# BME280-Breakout_v12.net
KiCad netlist of a schematic drawn in EAGLE
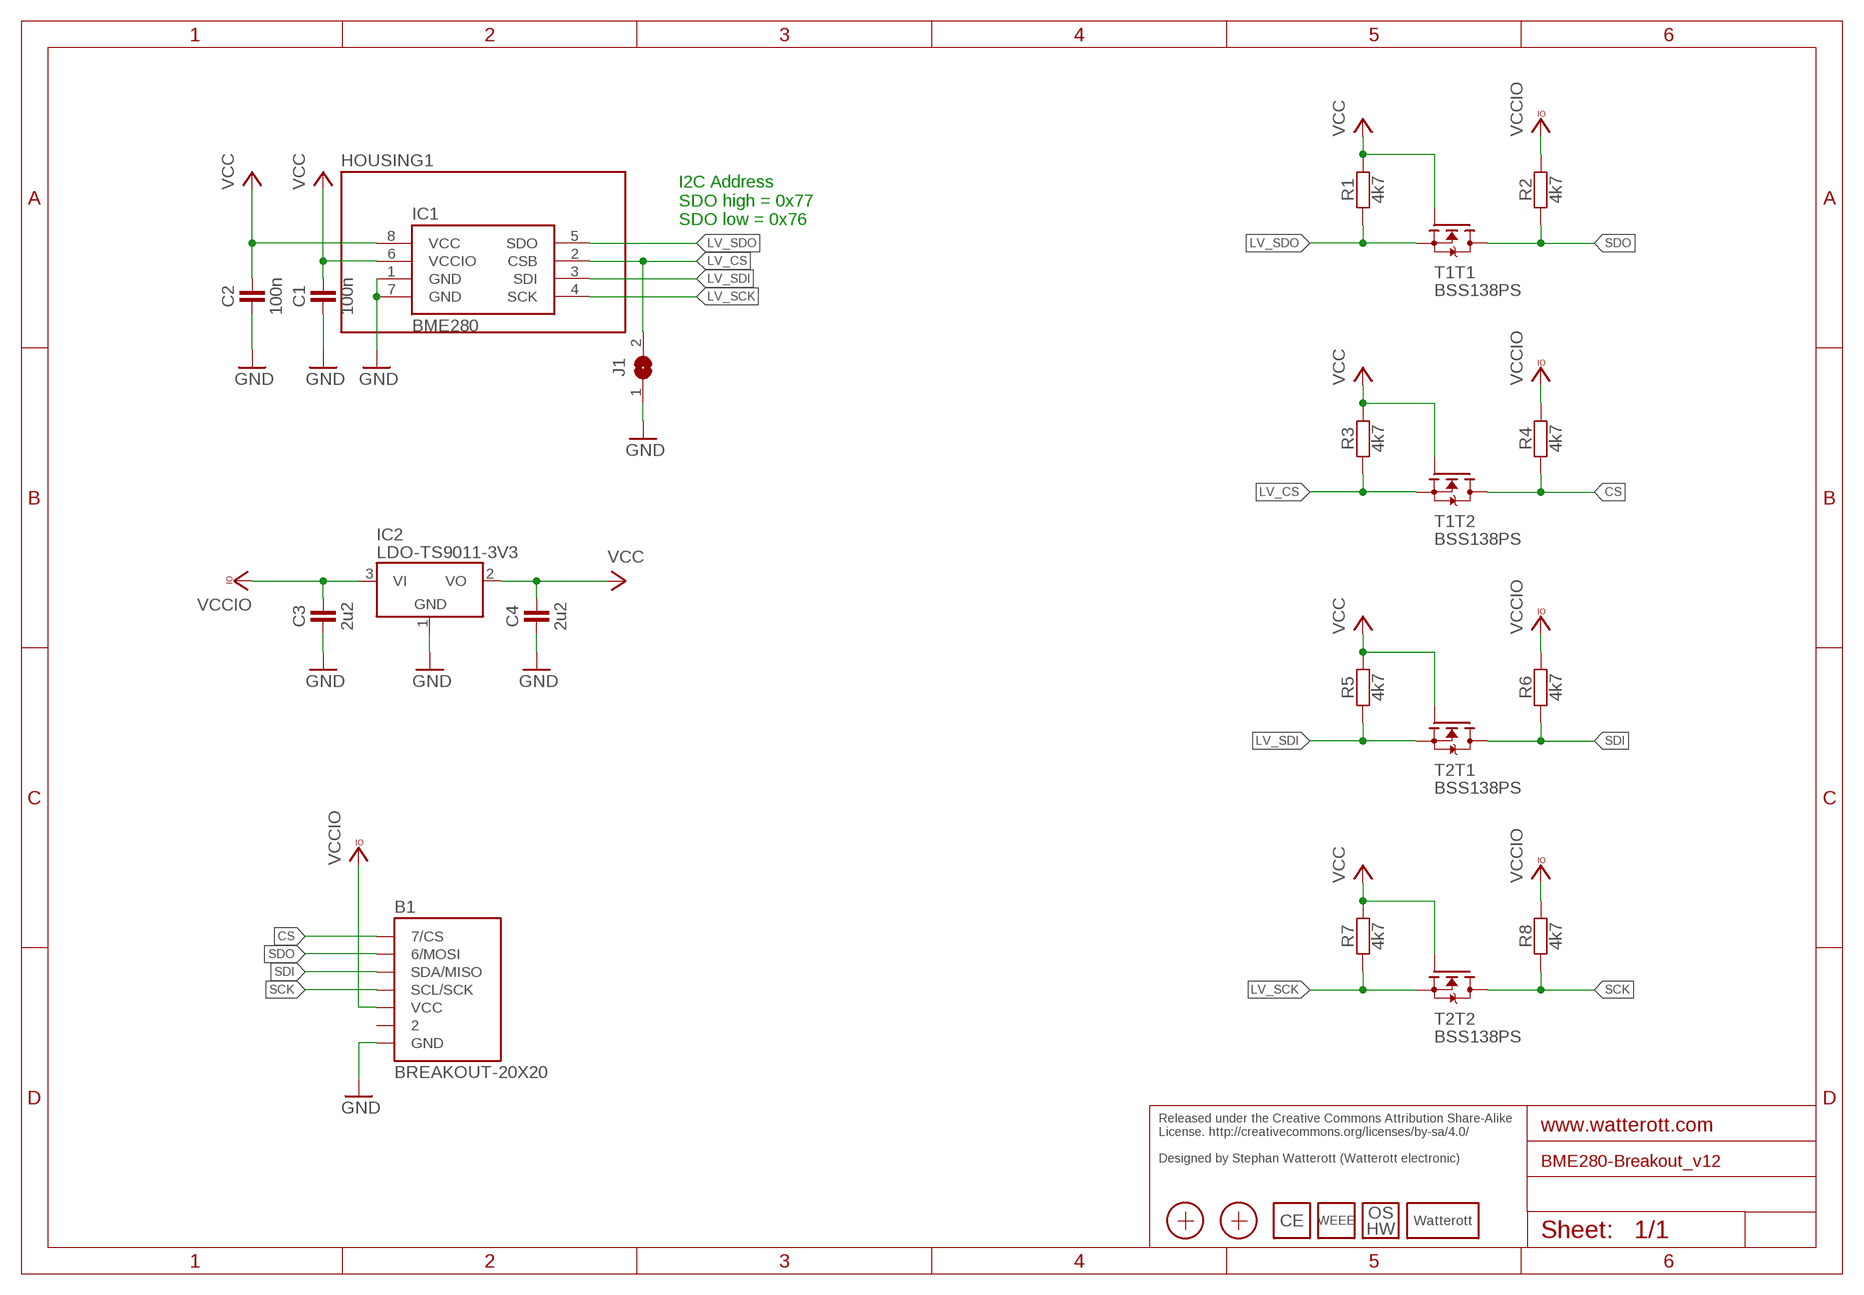
[diagram p0: schematic, sheet 1]

(export (version "E")
  (design (tool "Eeschema 10.0.6"))
  (components
    (comp (ref "B1")
      (value "BREAKOUT-20X20")
      (footprint "eagle-import:BREAKOUT-20X20")
      (libsource (lib "eagle-import") (part "BREAKOUT-20X20"))
    )
    (comp (ref "C1")
      (value "100n")
      (footprint "eagle-import:C0402")
      (libsource (lib "eagle-import") (part "CAPACITOR-0402"))
    )
    (comp (ref "C2")
      (value "100n")
      (footprint "eagle-import:C0402")
      (libsource (lib "eagle-import") (part "CAPACITOR-0402"))
    )
    (comp (ref "C3")
      (value "2u2")
      (footprint "eagle-import:C0402")
      (libsource (lib "eagle-import") (part "CAPACITOR-0402"))
    )
    (comp (ref "C4")
      (value "2u2")
      (footprint "eagle-import:C0402")
      (libsource (lib "eagle-import") (part "CAPACITOR-0402"))
    )
    (comp (ref "HOUSING1")
      (value "SF2")
      (footprint "eagle-import:SF2")
      (libsource (lib "eagle-import") (part "SF2"))
    )
    (comp (ref "IC1")
      (value "BME280")
      (footprint "eagle-import:CAVITY_MEMS")
      (libsource (lib "eagle-import") (part "BME280"))
    )
    (comp (ref "IC2")
      (value "LDO-TS9011-3V3")
      (footprint "eagle-import:SOT23")
      (libsource (lib "eagle-import") (part "LDO-TS9011-3V3"))
    )
    (comp (ref "J1")
      (value "JUMPER2-0603")
      (footprint "eagle-import:JUMPER2-0603")
      (libsource (lib "eagle-import") (part "JUMPER2-0603"))
    )
    (comp (ref "LOGO3")
      (value "LOGO_CE-2")
      (footprint "eagle-import:CE_2MM")
      (libsource (lib "eagle-import") (part "LOGO_CE-2"))
    )
    (comp (ref "LOGO4")
      (value "LOGO_WEEE-4")
      (footprint "eagle-import:WEEE_4MM")
      (libsource (lib "eagle-import") (part "LOGO_WEEE-4"))
    )
    (comp (ref "LOGO5")
      (value "LOGO_SPARK-2")
      (footprint "eagle-import:SPARK_2MM")
      (libsource (lib "eagle-import") (part "LOGO_SPARK-2"))
    )
    (comp (ref "LOGO6")
      (value "LOGO_OSHW-2")
      (footprint "eagle-import:OSHW_2MM")
      (libsource (lib "eagle-import") (part "LOGO_OSHW-2"))
    )
    (comp (ref "R1")
      (value "4k7")
      (footprint "eagle-import:C0402")
      (libsource (lib "eagle-import") (part "RESISTOR-0402"))
    )
    (comp (ref "R2")
      (value "4k7")
      (footprint "eagle-import:C0402")
      (libsource (lib "eagle-import") (part "RESISTOR-0402"))
    )
    (comp (ref "R3")
      (value "4k7")
      (footprint "eagle-import:C0402")
      (libsource (lib "eagle-import") (part "RESISTOR-0402"))
    )
    (comp (ref "R4")
      (value "4k7")
      (footprint "eagle-import:C0402")
      (libsource (lib "eagle-import") (part "RESISTOR-0402"))
    )
    (comp (ref "R5")
      (value "4k7")
      (footprint "eagle-import:C0402")
      (libsource (lib "eagle-import") (part "RESISTOR-0402"))
    )
    (comp (ref "R6")
      (value "4k7")
      (footprint "eagle-import:C0402")
      (libsource (lib "eagle-import") (part "RESISTOR-0402"))
    )
    (comp (ref "R7")
      (value "4k7")
      (footprint "eagle-import:C0402")
      (libsource (lib "eagle-import") (part "RESISTOR-0402"))
    )
    (comp (ref "R8")
      (value "4k7")
      (footprint "eagle-import:C0402")
      (libsource (lib "eagle-import") (part "RESISTOR-0402"))
    )
    (comp (ref "T1")
      (value "BSS138PS")
      (footprint "eagle-import:SOT363")
      (libsource (lib "eagle-import") (part "BSS138PS"))
    )
    (comp (ref "T2")
      (value "BSS138PS")
      (footprint "eagle-import:SOT363")
      (libsource (lib "eagle-import") (part "BSS138PS"))
    )
    (comp (ref "X1")
      (value "PASSER-07")
      (footprint "eagle-import:PASSER_07MM")
      (libsource (lib "eagle-import") (part "PASSER-07"))
    )
    (comp (ref "X2")
      (value "PASSER-07")
      (footprint "eagle-import:PASSER_07MM")
      (libsource (lib "eagle-import") (part "PASSER-07"))
    )
  )
  (nets
    (net (code "1") (name "CS") (class "Default")
      (node (ref "B1") (pin "CS") (pinfunction "7/CS_CS") (pintype "bidirectional"))
      (node (ref "R4") (pin "1") (pinfunction "1_1") (pintype "passive"))
      (node (ref "T1") (pin "3") (pinfunction "D_3") (pintype "passive"))
    )
    (net (code "2") (name "GND") (class "Default")
      (node (ref "B1") (pin "GND") (pinfunction "GND_GND") (pintype "power_in"))
      (node (ref "C1") (pin "1") (pinfunction "1_1") (pintype "passive"))
      (node (ref "C2") (pin "1") (pinfunction "1_1") (pintype "passive"))
      (node (ref "C3") (pin "1") (pinfunction "1_1") (pintype "passive"))
      (node (ref "C4") (pin "1") (pinfunction "1_1") (pintype "passive"))
      (node (ref "IC1") (pin "1") (pinfunction "GND_1") (pintype "power_in"))
      (node (ref "IC1") (pin "7") (pinfunction "GND_7") (pintype "power_in"))
      (node (ref "IC2") (pin "1") (pinfunction "GND_1") (pintype "passive"))
      (node (ref "J1") (pin "1") (pinfunction "1_1") (pintype "passive"))
    )
    (net (code "3") (name "LV_CS") (class "Default")
      (node (ref "IC1") (pin "2") (pinfunction "CSB_2") (pintype "input"))
      (node (ref "J1") (pin "2") (pinfunction "2_2") (pintype "passive"))
      (node (ref "R3") (pin "1") (pinfunction "1_1") (pintype "passive"))
      (node (ref "T1") (pin "4") (pinfunction "S_4") (pintype "passive"))
    )
    (net (code "4") (name "LV_SCK") (class "Default")
      (node (ref "IC1") (pin "4") (pinfunction "SCK_4") (pintype "bidirectional"))
      (node (ref "R7") (pin "1") (pinfunction "1_1") (pintype "passive"))
      (node (ref "T2") (pin "4") (pinfunction "S_4") (pintype "passive"))
    )
    (net (code "5") (name "LV_SDI") (class "Default")
      (node (ref "IC1") (pin "3") (pinfunction "SDI_3") (pintype "bidirectional"))
      (node (ref "R5") (pin "1") (pinfunction "1_1") (pintype "passive"))
      (node (ref "T2") (pin "1") (pinfunction "S_1") (pintype "passive"))
    )
    (net (code "6") (name "LV_SDO") (class "Default")
      (node (ref "IC1") (pin "5") (pinfunction "SDO_5") (pintype "bidirectional"))
      (node (ref "R1") (pin "1") (pinfunction "1_1") (pintype "passive"))
      (node (ref "T1") (pin "1") (pinfunction "S_1") (pintype "passive"))
    )
    (net (code "7") (name "SCK") (class "Default")
      (node (ref "B1") (pin "SCL/SCK") (pinfunction "SCL/SCK_SCL/SCK") (pintype "bidirectional"))
      (node (ref "R8") (pin "1") (pinfunction "1_1") (pintype "passive"))
      (node (ref "T2") (pin "3") (pinfunction "D_3") (pintype "passive"))
    )
    (net (code "8") (name "SDI") (class "Default")
      (node (ref "B1") (pin "SDA/MISO") (pinfunction "SDA/MISO_SDA/MISO") (pintype "bidirectional"))
      (node (ref "R6") (pin "1") (pinfunction "1_1") (pintype "passive"))
      (node (ref "T2") (pin "6") (pinfunction "D_6") (pintype "passive"))
    )
    (net (code "9") (name "SDO") (class "Default")
      (node (ref "B1") (pin "MOSI") (pinfunction "6/MOSI_MOSI") (pintype "bidirectional"))
      (node (ref "R2") (pin "1") (pinfunction "1_1") (pintype "passive"))
      (node (ref "T1") (pin "6") (pinfunction "D_6") (pintype "passive"))
    )
    (net (code "10") (name "VCC") (class "Default")
      (node (ref "C1") (pin "2") (pinfunction "2_2") (pintype "passive"))
      (node (ref "C2") (pin "2") (pinfunction "2_2") (pintype "passive"))
      (node (ref "C4") (pin "2") (pinfunction "2_2") (pintype "passive"))
      (node (ref "IC1") (pin "6") (pinfunction "VCCIO_6") (pintype "power_in"))
      (node (ref "IC1") (pin "8") (pinfunction "VCC_8") (pintype "power_in"))
      (node (ref "IC2") (pin "2") (pinfunction "VO_2") (pintype "passive"))
      (node (ref "R1") (pin "2") (pinfunction "2_2") (pintype "passive"))
      (node (ref "R3") (pin "2") (pinfunction "2_2") (pintype "passive"))
      (node (ref "R5") (pin "2") (pinfunction "2_2") (pintype "passive"))
      (node (ref "R7") (pin "2") (pinfunction "2_2") (pintype "passive"))
      (node (ref "T1") (pin "2") (pinfunction "G_2") (pintype "passive"))
      (node (ref "T1") (pin "5") (pinfunction "G_5") (pintype "passive"))
      (node (ref "T2") (pin "2") (pinfunction "G_2") (pintype "passive"))
      (node (ref "T2") (pin "5") (pinfunction "G_5") (pintype "passive"))
    )
    (net (code "11") (name "VCCIO") (class "Default")
      (node (ref "B1") (pin "VCC") (pinfunction "VCC_VCC") (pintype "power_in"))
      (node (ref "C3") (pin "2") (pinfunction "2_2") (pintype "passive"))
      (node (ref "IC2") (pin "3") (pinfunction "VI_3") (pintype "input"))
      (node (ref "R2") (pin "2") (pinfunction "2_2") (pintype "passive"))
      (node (ref "R4") (pin "2") (pinfunction "2_2") (pintype "passive"))
      (node (ref "R6") (pin "2") (pinfunction "2_2") (pintype "passive"))
      (node (ref "R8") (pin "2") (pinfunction "2_2") (pintype "passive"))
    )
    (net (code "12") (name "unconnected-(B1-Pad2)") (class "Default")
      (node (ref "B1") (pin "2") (pinfunction "2_2") (pintype "bidirectional"))
    )
  )
)
